# Power.net
KiCad netlist of a schematic drawn in Altium Designer
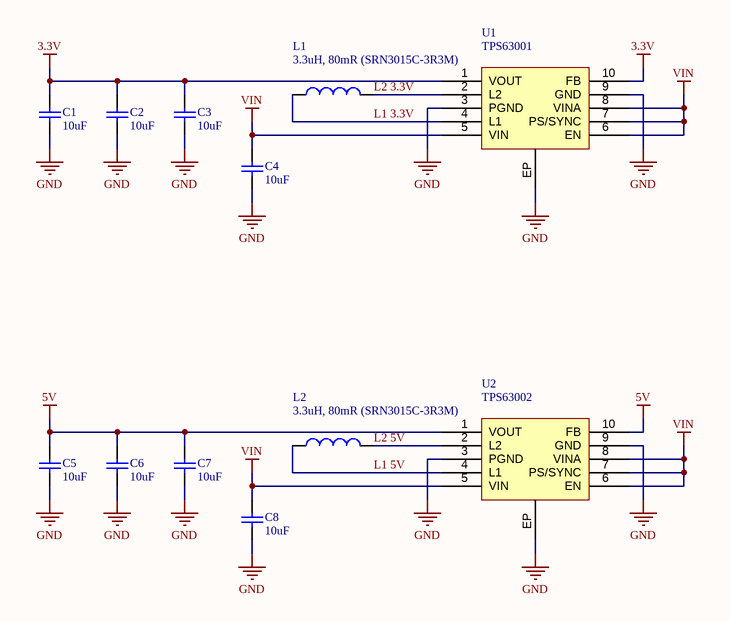
[diagram p0: Power.SchDoc]

(export (version "E")
  (design (tool "Eeschema 10.0.6"))
  (components
    (comp (ref "C1") (value "10uF") (footprint "Capacitor 0402") (libsource (lib "x-io") (part "Capacitor")))
    (comp (ref "C2") (value "10uF") (footprint "Capacitor 0402") (libsource (lib "x-io") (part "Capacitor")))
    (comp (ref "C3") (value "10uF") (footprint "Capacitor 0402") (libsource (lib "x-io") (part "Capacitor")))
    (comp (ref "C4") (value "10uF") (footprint "Capacitor 0402") (libsource (lib "x-io") (part "Capacitor")))
    (comp (ref "C5") (value "10uF") (footprint "Capacitor 0402") (libsource (lib "x-io") (part "Capacitor")))
    (comp (ref "C6") (value "10uF") (footprint "Capacitor 0402") (libsource (lib "x-io") (part "Capacitor")))
    (comp (ref "C7") (value "10uF") (footprint "Capacitor 0402") (libsource (lib "x-io") (part "Capacitor")))
    (comp (ref "C8") (value "10uF") (footprint "Capacitor 0402") (libsource (lib "x-io") (part "Capacitor")))
    (comp (ref "L1")
      (value "3.3uH, 80mR (SRN3015C-3R3M)")
      (footprint "SRN3015C")
      (libsource (lib "x-io") (part "Inductor"))
    )
    (comp (ref "L2")
      (value "3.3uH, 80mR (SRN3015C-3R3M)")
      (footprint "SRN3015C")
      (libsource (lib "x-io") (part "Inductor"))
    )
    (comp (ref "U1") (value "TPS63001") (footprint "WSON-10") (libsource (lib "x-io") (part "TPS630XX")))
    (comp (ref "U2") (value "TPS63002") (footprint "WSON-10") (libsource (lib "x-io") (part "TPS630XX")))
  )
  (nets
    (net (code "1") (name "/L1 3.3V") (class "Default")
      (node (ref "L1") (pin "1") (pinfunction "1_1") (pintype "passive"))
      (node (ref "U1") (pin "4") (pinfunction "L1_4") (pintype "passive"))
    )
    (net (code "2") (name "/L1 5V") (class "Default")
      (node (ref "L2") (pin "1") (pinfunction "1_1") (pintype "passive"))
      (node (ref "U2") (pin "4") (pinfunction "L1_4") (pintype "passive"))
    )
    (net (code "3") (name "/L2 3.3V") (class "Default")
      (node (ref "L1") (pin "2") (pinfunction "2_2") (pintype "passive"))
      (node (ref "U1") (pin "2") (pinfunction "L2_2") (pintype "passive"))
    )
    (net (code "4") (name "/L2 5V") (class "Default")
      (node (ref "L2") (pin "2") (pinfunction "2_2") (pintype "passive"))
      (node (ref "U2") (pin "2") (pinfunction "L2_2") (pintype "passive"))
    )
    (net (code "5") (name "3.3V") (class "Default")
      (node (ref "C1") (pin "2") (pinfunction "2_2") (pintype "passive"))
      (node (ref "C2") (pin "2") (pinfunction "2_2") (pintype "passive"))
      (node (ref "C3") (pin "2") (pinfunction "2_2") (pintype "passive"))
      (node (ref "U1") (pin "1") (pinfunction "VOUT_1") (pintype "passive"))
      (node (ref "U1") (pin "10") (pinfunction "FB_10") (pintype "passive"))
    )
    (net (code "6") (name "5V") (class "Default")
      (node (ref "C5") (pin "2") (pinfunction "2_2") (pintype "passive"))
      (node (ref "C6") (pin "2") (pinfunction "2_2") (pintype "passive"))
      (node (ref "C7") (pin "2") (pinfunction "2_2") (pintype "passive"))
      (node (ref "U2") (pin "1") (pinfunction "VOUT_1") (pintype "passive"))
      (node (ref "U2") (pin "10") (pinfunction "FB_10") (pintype "passive"))
    )
    (net (code "7") (name "GND") (class "Default")
      (node (ref "C1") (pin "1") (pinfunction "1_1") (pintype "passive"))
      (node (ref "C2") (pin "1") (pinfunction "1_1") (pintype "passive"))
      (node (ref "C3") (pin "1") (pinfunction "1_1") (pintype "passive"))
      (node (ref "C4") (pin "1") (pinfunction "1_1") (pintype "passive"))
      (node (ref "C5") (pin "1") (pinfunction "1_1") (pintype "passive"))
      (node (ref "C6") (pin "1") (pinfunction "1_1") (pintype "passive"))
      (node (ref "C7") (pin "1") (pinfunction "1_1") (pintype "passive"))
      (node (ref "C8") (pin "1") (pinfunction "1_1") (pintype "passive"))
      (node (ref "U1") (pin "3") (pinfunction "PGND_3") (pintype "passive"))
      (node (ref "U1") (pin "9") (pinfunction "GND_9") (pintype "passive"))
      (node (ref "U1") (pin "EP") (pinfunction "EP_EP") (pintype "passive"))
      (node (ref "U2") (pin "3") (pinfunction "PGND_3") (pintype "passive"))
      (node (ref "U2") (pin "9") (pinfunction "GND_9") (pintype "passive"))
      (node (ref "U2") (pin "EP") (pinfunction "EP_EP") (pintype "passive"))
    )
    (net (code "8") (name "VIN") (class "Default")
      (node (ref "C4") (pin "2") (pinfunction "2_2") (pintype "passive"))
      (node (ref "C8") (pin "2") (pinfunction "2_2") (pintype "passive"))
      (node (ref "U1") (pin "5") (pinfunction "VIN_5") (pintype "passive"))
      (node (ref "U1") (pin "6") (pinfunction "EN_6") (pintype "passive"))
      (node (ref "U1") (pin "7") (pinfunction "PS/SYNC_7") (pintype "passive"))
      (node (ref "U1") (pin "8") (pinfunction "VINA_8") (pintype "passive"))
      (node (ref "U2") (pin "5") (pinfunction "VIN_5") (pintype "passive"))
      (node (ref "U2") (pin "6") (pinfunction "EN_6") (pintype "passive"))
      (node (ref "U2") (pin "7") (pinfunction "PS/SYNC_7") (pintype "passive"))
      (node (ref "U2") (pin "8") (pinfunction "VINA_8") (pintype "passive"))
    )
  )
)
